# MAIN.net
KiCad netlist of a schematic drawn in Altium Designer
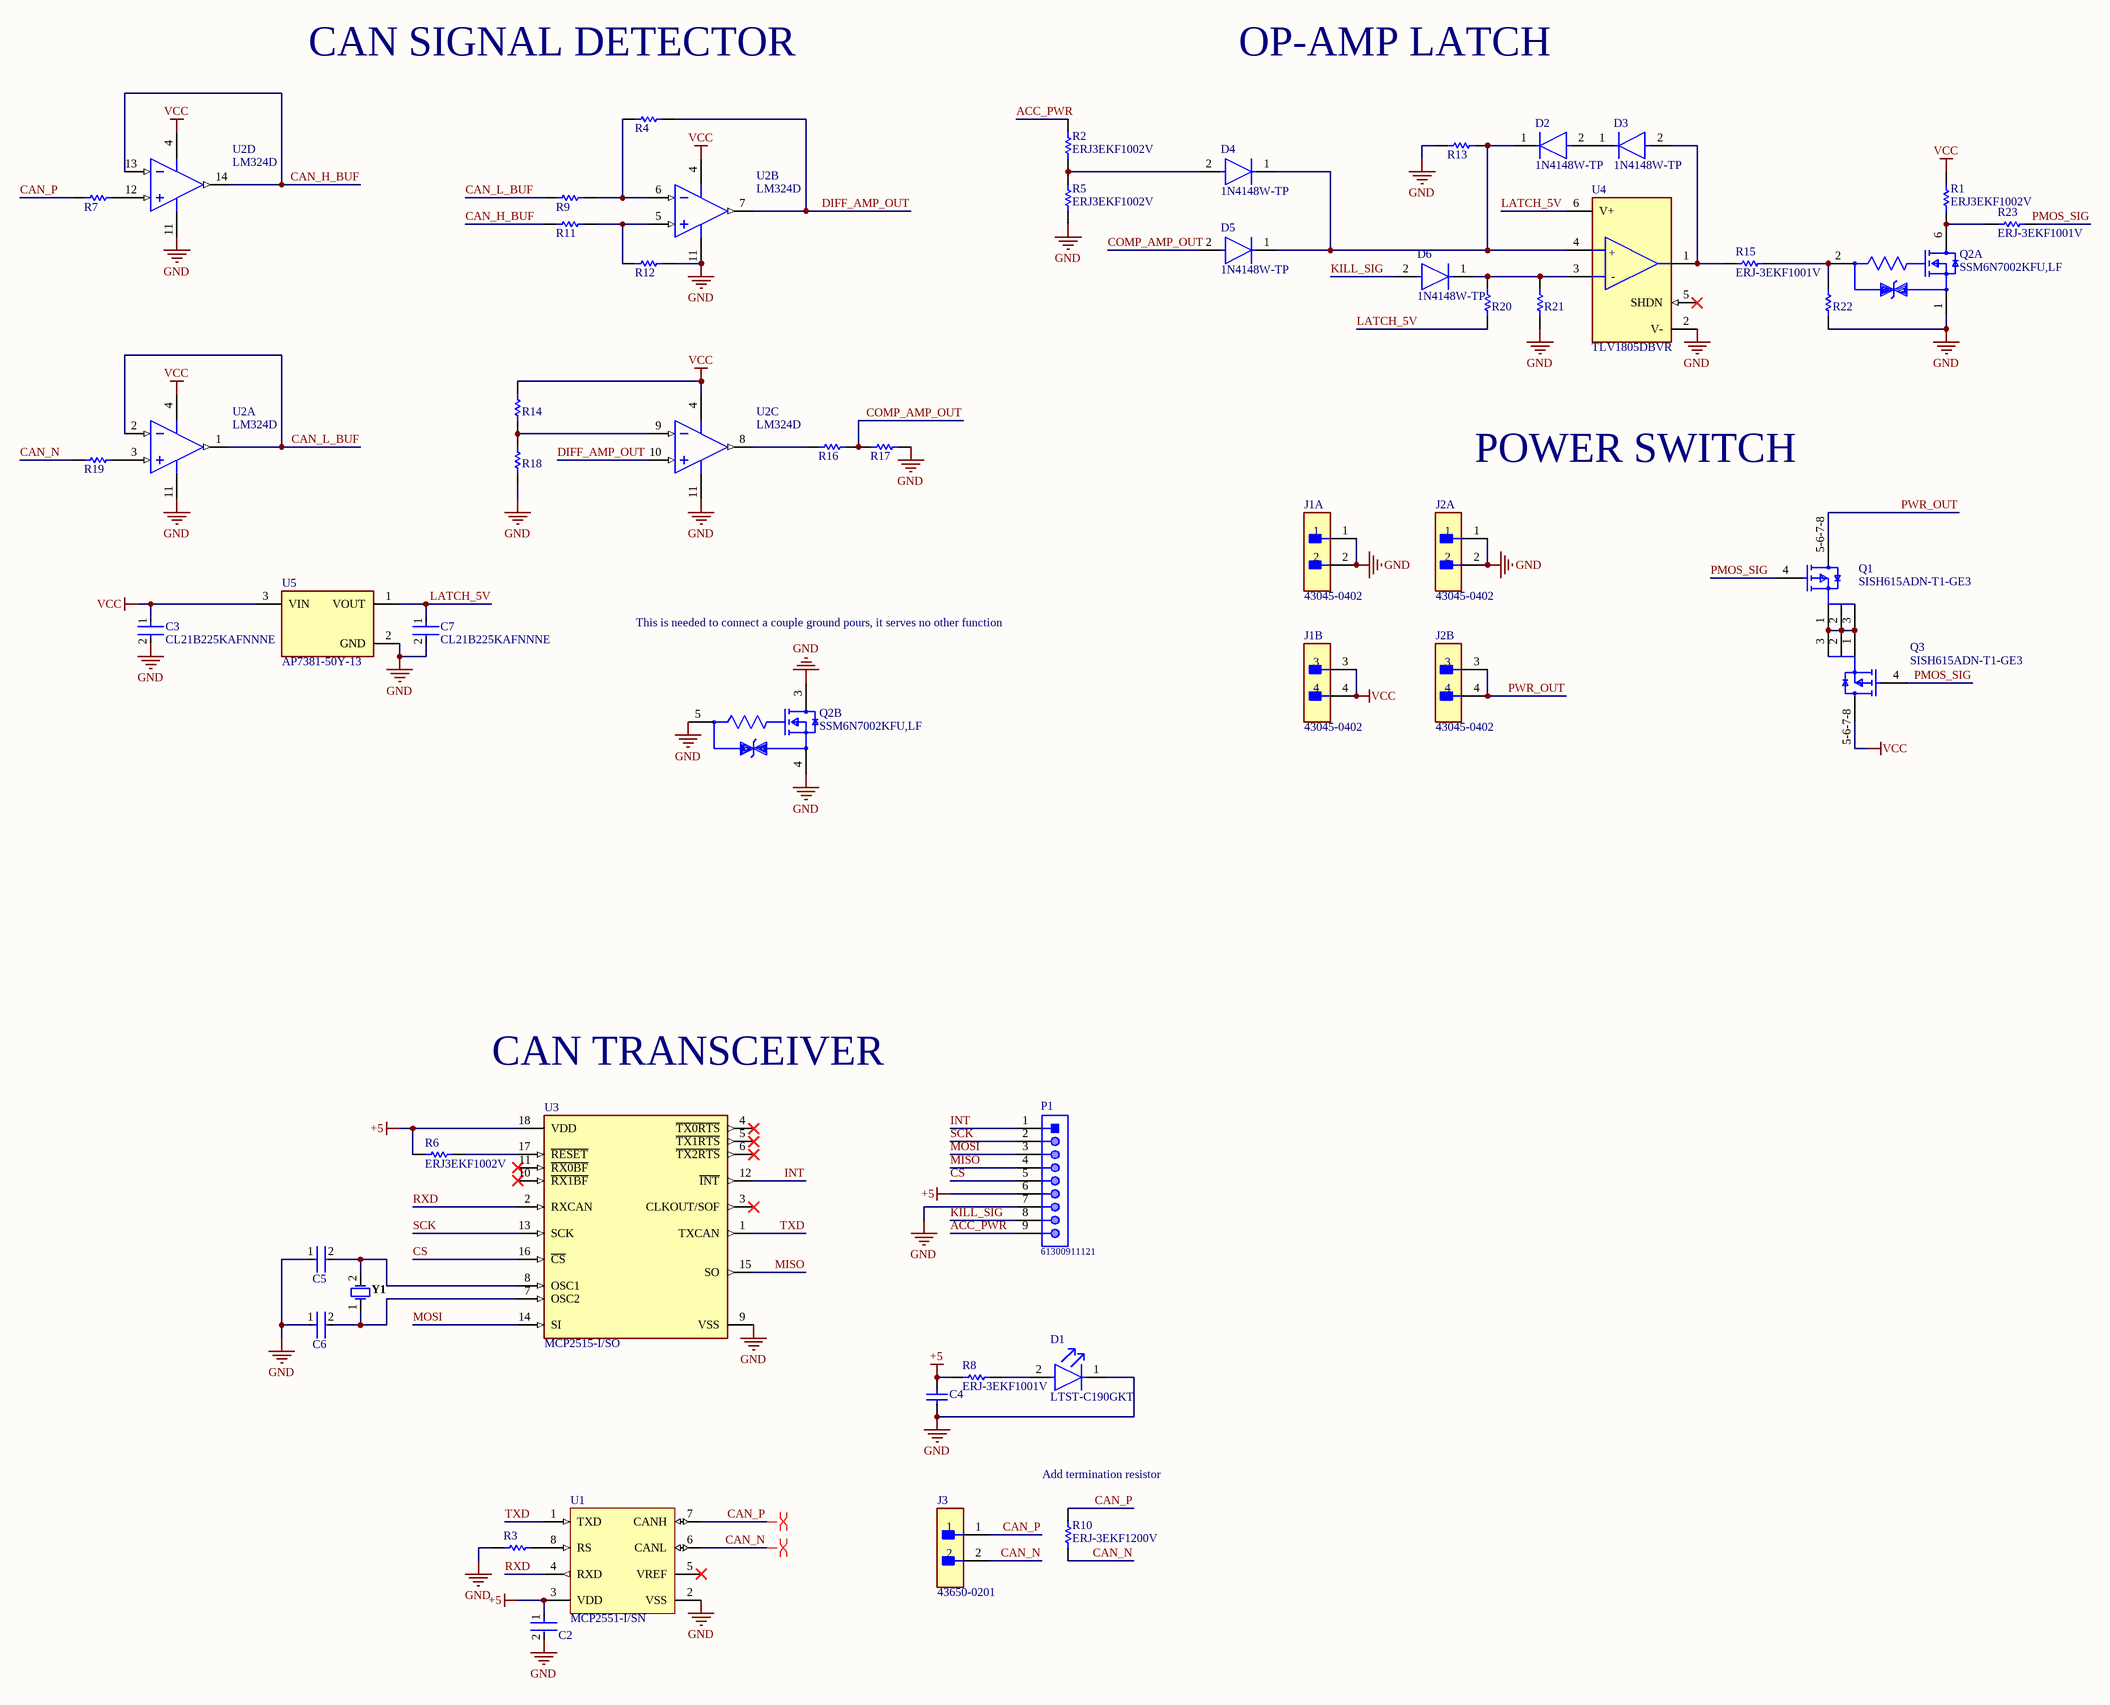
[diagram p0: MAIN.SchDoc]

(export (version "E")
  (design (tool "Eeschema 10.0.6"))
  (components
    (comp (ref "C2")
      (value "C0402C104K8PACTU")
      (footprint "FP-C0402-BB-MFG")
      (description "CAP CER 0.1UF 10V X5R 0402")
      (fields (field (name "MANUFACTURER") "Kemet") (field (name "TOLERANCE") "0.1"))
      (libsource (lib "Altium Content Vault") (part "b4654b650e69147ec39a6b967a45e02"))
    )
    (comp (ref "C3")
      (value "CL21B225KAFNNNE")
      (footprint "FP-0805-L_2_01_0_2-W_1_25-IPC_B")
      (fields (field (name "TOLERANCE") "10%") (field (name "VOLTAGE") "25V"))
      (libsource (lib "Altium Content Vault") (part "02cd4be3c70576c341d710602a673aa"))
    )
    (comp (ref "C4")
      (value "1206GC102KAT1A")
      (footprint "AVX-1206-2_L")
      (description "Chip Capacitor, 1 nF, +/- 10%, -55 to 125 degC, 1206 (3216 Metric), RoHS, Tape and Reel")
      (fields (field (name "TOLERANCE") "10%") (field (name "MANUFACTURER") "AVX"))
      (libsource (lib "Altium Content Vault") (part "CAP-NP-2"))
    )
    (comp (ref "C5")
      (value "GRM188R60J106ME47D")
      (footprint "FP-GRM188-0_1-e0_2_0_55-IPC_A")
      (description "Chip Multilayer Ceramic Capacitors for General Purpose, 0603, 10uF, X5R, 15%, 20%, 6.3V")
      (fields (field (name "VOLTAGE") "6.3V") (field (name "TOLERANCE") "20%"))
      (libsource (lib "Altium Content Vault") (part "02cd4be3c70576c341d710602a673aa"))
    )
    (comp (ref "C6")
      (value "GRM188R60J106ME47D")
      (footprint "FP-GRM188-0_1-e0_2_0_55-IPC_A")
      (description "Chip Multilayer Ceramic Capacitors for General Purpose, 0603, 10uF, X5R, 15%, 20%, 6.3V")
      (fields (field (name "VOLTAGE") "6.3V") (field (name "TOLERANCE") "20%"))
      (libsource (lib "Altium Content Vault") (part "02cd4be3c70576c341d710602a673aa"))
    )
    (comp (ref "C7")
      (value "CL21B225KAFNNNE")
      (footprint "FP-0805-L_2_01_0_2-W_1_25-IPC_B")
      (fields (field (name "TOLERANCE") "10%") (field (name "VOLTAGE") "25V"))
      (libsource (lib "Altium Content Vault") (part "02cd4be3c70576c341d710602a673aa"))
    )
    (comp (ref "D1")
      (value "LTST-C190GKT")
      (footprint "FP-LTST-C190GKT-MFG")
      (description "LED GREEN CLEAR CHIP SMD")
      (fields (field (name "VOLTAGE") "2V"))
      (libsource (lib "Altium Content Vault") (part "8706943c75ba83719d021d2fdc84c58"))
    )
    (comp (ref "D2")
      (value "1N4148W-TP")
      (footprint "FP-SOD-123-IPC_A")
      (description "DIODE GEN PURP 100V 150MA SOD123")
      (libsource (lib "Altium Content Vault") (part "d7152d700b627762746794eb795d46e"))
    )
    (comp (ref "D3")
      (value "1N4148W-TP")
      (footprint "FP-SOD-123-IPC_A")
      (description "DIODE GEN PURP 100V 150MA SOD123")
      (libsource (lib "Altium Content Vault") (part "d7152d700b627762746794eb795d46e"))
    )
    (comp (ref "D4")
      (value "1N4148W-TP")
      (footprint "FP-SOD-123-IPC_A")
      (description "DIODE GEN PURP 100V 150MA SOD123")
      (libsource (lib "Altium Content Vault") (part "d7152d700b627762746794eb795d46e"))
    )
    (comp (ref "D5")
      (value "1N4148W-TP")
      (footprint "FP-SOD-123-IPC_A")
      (description "DIODE GEN PURP 100V 150MA SOD123")
      (libsource (lib "Altium Content Vault") (part "d7152d700b627762746794eb795d46e"))
    )
    (comp (ref "D6")
      (value "1N4148W-TP")
      (footprint "FP-SOD-123-IPC_A")
      (description "DIODE GEN PURP 100V 150MA SOD123")
      (libsource (lib "Altium Content Vault") (part "d7152d700b627762746794eb795d46e"))
    )
    (comp (ref "J1")
      (value "43045-0402")
      (footprint "FP-43045-0402-MFG")
      (description "CONN HEADER R/A 4POS 3MM")
      (libsource (lib "Altium Content Vault") (part "ac72c5313ea981db199dbd0e8237b04"))
    )
    (comp (ref "J2")
      (value "43045-0402")
      (footprint "FP-43045-0402-MFG")
      (description "CONN HEADER R/A 4POS 3MM")
      (libsource (lib "Altium Content Vault") (part "ac72c5313ea981db199dbd0e8237b04"))
    )
    (comp (ref "J3")
      (value "43650-0201")
      (footprint "FP-43650-0201-MFG")
      (description "CONN HEADER R/A 2POS 3MM")
      (libsource (lib "Altium Content Vault") (part "3bc925449376181038e59eaffc5286c"))
    )
    (comp (ref "P1")
      (value "61300911121")
      (footprint "61300911121")
      (description "THT Vertical Pin Header WR-PHD, Pitch 2.54 mm, Single Row, 9 pins")
      (fields (field (name "MANUFACTURER") "Wurth Elektronik") (field (name "PUBLISHER") "WurthElektronik"))
      (libsource (lib "Altium Content Vault") (part "WE-CN-1P-M-R9"))
    )
    (comp (ref "Q1")
      (value "SISH615ADN-T1-GE3")
      (footprint "SISH615ADN-T1-GE3-Footprint-1")
      (description "Trans MOSFET P-CH 20V 22.1A 8-Pin PowerPAK 1212 EP T/R")
      (libsource (lib "uORocketry Hardware") (part "SISH615ADN-T1-GE3-Symbol-1"))
    )
    (comp (ref "Q2")
      (value "SSM6N7002KFU,LF")
      (footprint "FP-SSOP6-P-0_65A-MFG")
      (description "MOSFET 2N-CH 60V 0.3A")
      (libsource (lib "Altium Content Vault") (part "088aa6ac103fdeebe0d1c52ece6b7b9"))
    )
    (comp (ref "Q3")
      (value "SISH615ADN-T1-GE3")
      (footprint "SISH615ADN-T1-GE3-Footprint-1")
      (description "Trans MOSFET P-CH 20V 22.1A 8-Pin PowerPAK 1212 EP T/R")
      (libsource (lib "uORocketry Hardware") (part "SISH615ADN-T1-GE3-Symbol-1"))
    )
    (comp (ref "R1")
      (value "ERJ3EKF1002V")
      (footprint "RESC1609X55X30LL15T15")
      (description "Chip Resistor, 10 KOhm, +/- 1%, 0.1 W, -55 to 155 degC, 0603 (1608 Metric), RoHS, Tape and Reel")
      (fields (field (name "TOLERANCE") "1%") (field (name "MANUFACTURER") "Panasonic"))
      (libsource (lib "Altium Content Vault") (part "RES-2"))
    )
    (comp (ref "R2")
      (value "ERJ3EKF1002V")
      (footprint "RESC1609X55X30LL15T15")
      (description "Chip Resistor, 10 KOhm, +/- 1%, 0.1 W, -55 to 155 degC, 0603 (1608 Metric), RoHS, Tape and Reel")
      (fields (field (name "TOLERANCE") "1%") (field (name "MANUFACTURER") "Panasonic"))
      (libsource (lib "Altium Content Vault") (part "RES-2"))
    )
    (comp (ref "R3")
      (value "ERJ3EKF1002V")
      (footprint "RESC1609X55X30LL15T15")
      (description "Chip Resistor, 10 KOhm, +/- 1%, 0.1 W, -55 to 155 degC, 0603 (1608 Metric), RoHS, Tape and Reel")
      (fields (field (name "TOLERANCE") "1%") (field (name "MANUFACTURER") "Panasonic"))
      (libsource (lib "Altium Content Vault") (part "RES-2"))
    )
    (comp (ref "R4")
      (value "ERJ3EKF1002V")
      (footprint "RESC1609X55X30LL15T15")
      (description "Chip Resistor, 10 KOhm, +/- 1%, 0.1 W, -55 to 155 degC, 0603 (1608 Metric), RoHS, Tape and Reel")
      (fields (field (name "TOLERANCE") "1%") (field (name "MANUFACTURER") "Panasonic"))
      (libsource (lib "Altium Content Vault") (part "RES-2"))
    )
    (comp (ref "R5")
      (value "ERJ3EKF1002V")
      (footprint "RESC1609X55X30LL15T15")
      (description "Chip Resistor, 10 KOhm, +/- 1%, 0.1 W, -55 to 155 degC, 0603 (1608 Metric), RoHS, Tape and Reel")
      (fields (field (name "TOLERANCE") "1%") (field (name "MANUFACTURER") "Panasonic"))
      (libsource (lib "Altium Content Vault") (part "RES-2"))
    )
    (comp (ref "R6")
      (value "ERJ3EKF1002V")
      (footprint "RESC1609X55X30LL15T15")
      (description "Chip Resistor, 10 KOhm, +/- 1%, 0.1 W, -55 to 155 degC, 0603 (1608 Metric), RoHS, Tape and Reel")
      (fields (field (name "TOLERANCE") "1%") (field (name "MANUFACTURER") "Panasonic"))
      (libsource (lib "Altium Content Vault") (part "RES-2"))
    )
    (comp (ref "R7")
      (value "ERJ3EKF1002V")
      (footprint "RESC1609X55X30LL15T15")
      (description "Chip Resistor, 10 KOhm, +/- 1%, 0.1 W, -55 to 155 degC, 0603 (1608 Metric), RoHS, Tape and Reel")
      (fields (field (name "TOLERANCE") "1%") (field (name "MANUFACTURER") "Panasonic"))
      (libsource (lib "Altium Content Vault") (part "RES-2"))
    )
    (comp (ref "R8")
      (value "ERJ-3EKF1001V")
      (footprint "RESC1608X55X30LL15T15")
      (fields (field (name "MANUFACTURER") "Panasonic"))
      (libsource (lib "Altium Content Vault") (part "RES"))
    )
    (comp (ref "R9")
      (value "ERJ3EKF1002V")
      (footprint "RESC1609X55X30LL15T15")
      (description "Chip Resistor, 10 KOhm, +/- 1%, 0.1 W, -55 to 155 degC, 0603 (1608 Metric), RoHS, Tape and Reel")
      (fields (field (name "TOLERANCE") "1%") (field (name "MANUFACTURER") "Panasonic"))
      (libsource (lib "Altium Content Vault") (part "RES-2"))
    )
    (comp (ref "R10")
      (value "ERJ-3EKF1200V")
      (footprint "RESC1609X55X30ML15T15")
      (description "Chip Resistor, 120 Ohm, +/- 1%, 0.1 W, -55 to 155 degC, 0603 (1608 Metric), RoHS, Tape and Reel")
      (fields (field (name "TOLERANCE") "1%") (field (name "MANUFACTURER") "Panasonic"))
      (libsource (lib "Altium Content Vault") (part "RES-2"))
    )
    (comp (ref "R11")
      (value "ERJ3EKF1002V")
      (footprint "RESC1609X55X30LL15T15")
      (description "Chip Resistor, 10 KOhm, +/- 1%, 0.1 W, -55 to 155 degC, 0603 (1608 Metric), RoHS, Tape and Reel")
      (fields (field (name "TOLERANCE") "1%") (field (name "MANUFACTURER") "Panasonic"))
      (libsource (lib "Altium Content Vault") (part "RES-2"))
    )
    (comp (ref "R12")
      (value "ERJ3EKF1002V")
      (footprint "RESC1609X55X30LL15T15")
      (description "Chip Resistor, 10 KOhm, +/- 1%, 0.1 W, -55 to 155 degC, 0603 (1608 Metric), RoHS, Tape and Reel")
      (fields (field (name "TOLERANCE") "1%") (field (name "MANUFACTURER") "Panasonic"))
      (libsource (lib "Altium Content Vault") (part "RES-2"))
    )
    (comp (ref "R13")
      (value "ERJ3EKF1002V")
      (footprint "RESC1609X55X30LL15T15")
      (description "Chip Resistor, 10 KOhm, +/- 1%, 0.1 W, -55 to 155 degC, 0603 (1608 Metric), RoHS, Tape and Reel")
      (fields (field (name "TOLERANCE") "1%") (field (name "MANUFACTURER") "Panasonic"))
      (libsource (lib "Altium Content Vault") (part "RES-2"))
    )
    (comp (ref "R14")
      (value "ERJ3EKF1002V")
      (footprint "RESC1609X55X30LL15T15")
      (description "Chip Resistor, 10 KOhm, +/- 1%, 0.1 W, -55 to 155 degC, 0603 (1608 Metric), RoHS, Tape and Reel")
      (fields (field (name "TOLERANCE") "1%") (field (name "MANUFACTURER") "Panasonic"))
      (libsource (lib "Altium Content Vault") (part "RES-2"))
    )
    (comp (ref "R15")
      (value "ERJ-3EKF1001V")
      (footprint "RESC1608X55X30LL15T15")
      (fields (field (name "MANUFACTURER") "Panasonic"))
      (libsource (lib "Altium Content Vault") (part "RES"))
    )
    (comp (ref "R16")
      (value "ERJ3EKF1002V")
      (footprint "RESC1609X55X30LL15T15")
      (description "Chip Resistor, 10 KOhm, +/- 1%, 0.1 W, -55 to 155 degC, 0603 (1608 Metric), RoHS, Tape and Reel")
      (fields (field (name "TOLERANCE") "1%") (field (name "MANUFACTURER") "Panasonic"))
      (libsource (lib "Altium Content Vault") (part "RES-2"))
    )
    (comp (ref "R17")
      (value "ERJ3EKF1002V")
      (footprint "RESC1609X55X30LL15T15")
      (description "Chip Resistor, 10 KOhm, +/- 1%, 0.1 W, -55 to 155 degC, 0603 (1608 Metric), RoHS, Tape and Reel")
      (fields (field (name "TOLERANCE") "1%") (field (name "MANUFACTURER") "Panasonic"))
      (libsource (lib "Altium Content Vault") (part "RES-2"))
    )
    (comp (ref "R18")
      (value "ERJ-3EKF1001V")
      (footprint "RESC1608X55X30LL15T15")
      (fields (field (name "MANUFACTURER") "Panasonic"))
      (libsource (lib "Altium Content Vault") (part "RES"))
    )
    (comp (ref "R19")
      (value "ERJ3EKF1002V")
      (footprint "RESC1609X55X30LL15T15")
      (description "Chip Resistor, 10 KOhm, +/- 1%, 0.1 W, -55 to 155 degC, 0603 (1608 Metric), RoHS, Tape and Reel")
      (fields (field (name "TOLERANCE") "1%") (field (name "MANUFACTURER") "Panasonic"))
      (libsource (lib "Altium Content Vault") (part "RES-2"))
    )
    (comp (ref "R20")
      (value "ERJ3EKF1002V")
      (footprint "RESC1609X55X30LL15T15")
      (description "Chip Resistor, 10 KOhm, +/- 1%, 0.1 W, -55 to 155 degC, 0603 (1608 Metric), RoHS, Tape and Reel")
      (fields (field (name "TOLERANCE") "1%") (field (name "MANUFACTURER") "Panasonic"))
      (libsource (lib "Altium Content Vault") (part "RES-2"))
    )
    (comp (ref "R21")
      (value "ERJ3EKF1002V")
      (footprint "RESC1609X55X30LL15T15")
      (description "Chip Resistor, 10 KOhm, +/- 1%, 0.1 W, -55 to 155 degC, 0603 (1608 Metric), RoHS, Tape and Reel")
      (fields (field (name "TOLERANCE") "1%") (field (name "MANUFACTURER") "Panasonic"))
      (libsource (lib "Altium Content Vault") (part "RES-2"))
    )
    (comp (ref "R22")
      (value "ERJ3EKF1002V")
      (footprint "RESC1609X55X30LL15T15")
      (description "Chip Resistor, 10 KOhm, +/- 1%, 0.1 W, -55 to 155 degC, 0603 (1608 Metric), RoHS, Tape and Reel")
      (fields (field (name "TOLERANCE") "1%") (field (name "MANUFACTURER") "Panasonic"))
      (libsource (lib "Altium Content Vault") (part "RES-2"))
    )
    (comp (ref "R23")
      (value "ERJ-3EKF1001V")
      (footprint "RESC1608X55X30LL15T15")
      (fields (field (name "MANUFACTURER") "Panasonic"))
      (libsource (lib "Altium Content Vault") (part "RES"))
    )
    (comp (ref "U1")
      (value "MCP2551-I/SN")
      (footprint "MCHP-SN8_V")
      (fields (field (name "MANUFACTURER") "Microchip"))
      (libsource (lib "Altium Content Vault") (part "MCHP-MCP2551-SN8"))
    )
    (comp (ref "U2")
      (value "LM324D")
      (footprint "D0014A_L")
      (fields (field (name "MANUFACTURER") "Texas Instruments"))
      (libsource (lib "Altium Content Vault") (part "TI-LMX24_2902X-X14"))
    )
    (comp (ref "U3")
      (value "MCP2515-I/SO")
      (footprint "FP-C04-051-MFG")
      (description "IC CAN CONTROLLER W/SPI 18SOIC")
      (fields
        (field (name "MANUFACTURER") "Microchip")
        (field (name "OCTOPART") "https://octopart.com/mcp2515-i%2Fso-microchip-430187")
      )
      (libsource (lib "Altium Content Vault") (part "1c78ea6ff576bac94664e2637e1b479"))
    )
    (comp (ref "U4")
      (value "TLV1805DBVR")
      (footprint "FP-DBV0006A-IPC_C")
      (description "40V, RAIL-TO-RAIL INPUT, PUSH-PU")
      (libsource (lib "Altium Content Vault") (part "c7aa3bc3dbf0dc8b0b0354779bd1228"))
    )
    (comp (ref "U5")
      (value "AP7381-50Y-13")
      (footprint "FP-SOT89-MFG")
      (description "IC REG LINEAR 5V 150MA SOT89")
      (fields
        (field (name "MANUFACTURER") "Diodes Inc.")
        (field (name "OCTOPART") "https://octopart.com/ap7381-50y-13-diodes+inc.-87775116")
      )
      (libsource (lib "Altium Content Vault") (part "4c3da590f2d7b1882ad42f13e6d336b"))
    )
    (comp (ref "Y1")
      (value "FOXSLF/160-20")
      (footprint "FOX-FOXSLF160-20")
      (description "Resistance Weld Thru-Hole Crystal, 16 MHz, -20 to 70 degC, 2-Pin THD, RoHS, Bulk")
      (fields (field (name "TOLERANCE") "1%"))
      (libsource (lib "Altium Content Vault") (part "XTAL-1-2-2"))
    )
  )
  (nets
    (net (code "1") (name "+5") (class "Default")
      (node (ref "C2") (pin "1") (pinfunction "1_1") (pintype "passive"))
      (node (ref "C4") (pin "2") (pinfunction "2_2") (pintype "passive"))
      (node (ref "P1") (pin "6") (pinfunction "6_6") (pintype "passive"))
      (node (ref "R6") (pin "1") (pinfunction "1_1") (pintype "passive"))
      (node (ref "R8") (pin "2") (pinfunction "2_2") (pintype "passive"))
      (node (ref "U1") (pin "3") (pinfunction "VDD_3") (pintype "power_in"))
      (node (ref "U3") (pin "18") (pinfunction "VDD_18") (pintype "power_in"))
    )
    (net (code "2") (name "/ACC_PWR") (class "Default")
      (node (ref "P1") (pin "9") (pinfunction "9_9") (pintype "passive"))
      (node (ref "R2") (pin "2") (pinfunction "2_2") (pintype "passive"))
    )
    (net (code "3") (name "/CAN_H_BUF") (class "Default")
      (node (ref "R11") (pin "1") (pinfunction "1_1") (pintype "passive"))
      (node (ref "U2") (pin "13") (pinfunction "4IN-_13") (pintype "input"))
      (node (ref "U2") (pin "14") (pinfunction "4OUT_14") (pintype "output"))
    )
    (net (code "4") (name "/CAN_L_BUF") (class "Default")
      (node (ref "R9") (pin "1") (pinfunction "1_1") (pintype "passive"))
      (node (ref "U2") (pin "1") (pinfunction "1OUT_1") (pintype "output"))
      (node (ref "U2") (pin "2") (pinfunction "1IN-_2") (pintype "input"))
    )
    (net (code "5") (name "/CAN_N") (class "Default")
      (node (ref "J3") (pin "2") (pinfunction "2_2") (pintype "passive"))
      (node (ref "R10") (pin "1") (pinfunction "1_1") (pintype "passive"))
      (node (ref "R19") (pin "1") (pinfunction "1_1") (pintype "passive"))
      (node (ref "U1") (pin "6") (pinfunction "CANL_6") (pintype "bidirectional"))
    )
    (net (code "6") (name "/CAN_P") (class "Default")
      (node (ref "J3") (pin "1") (pinfunction "1_1") (pintype "passive"))
      (node (ref "R10") (pin "2") (pinfunction "2_2") (pintype "passive"))
      (node (ref "R7") (pin "1") (pinfunction "1_1") (pintype "passive"))
      (node (ref "U1") (pin "7") (pinfunction "CANH_7") (pintype "bidirectional"))
    )
    (net (code "7") (name "/COMP_AMP_OUT") (class "Default")
      (node (ref "D5") (pin "2") (pinfunction "A_2") (pintype "passive"))
      (node (ref "R16") (pin "1") (pinfunction "1_1") (pintype "passive"))
      (node (ref "R17") (pin "2") (pinfunction "2_2") (pintype "passive"))
    )
    (net (code "8") (name "/CS") (class "Default")
      (node (ref "P1") (pin "5") (pinfunction "5_5") (pintype "passive"))
      (node (ref "U3") (pin "16") (pinfunction "~{CS}_16") (pintype "input"))
    )
    (net (code "9") (name "/DIFF_AMP_OUT") (class "Default")
      (node (ref "R4") (pin "2") (pinfunction "2_2") (pintype "passive"))
      (node (ref "U2") (pin "10") (pinfunction "3IN+_10") (pintype "input"))
      (node (ref "U2") (pin "7") (pinfunction "2OUT_7") (pintype "output"))
    )
    (net (code "10") (name "/INT") (class "Default")
      (node (ref "P1") (pin "1") (pinfunction "1_1") (pintype "passive"))
      (node (ref "U3") (pin "12") (pinfunction "~{INT}_12") (pintype "output"))
    )
    (net (code "11") (name "/KILL_SIG") (class "Default")
      (node (ref "D6") (pin "2") (pinfunction "A_2") (pintype "passive"))
      (node (ref "P1") (pin "8") (pinfunction "8_8") (pintype "passive"))
    )
    (net (code "12") (name "/LATCH_5V") (class "Default")
      (node (ref "C7") (pin "1") (pinfunction "1_1") (pintype "passive"))
      (node (ref "R20") (pin "1") (pinfunction "1_1") (pintype "passive"))
      (node (ref "U4") (pin "6") (pinfunction "V+_6") (pintype "power_in"))
      (node (ref "U5") (pin "1") (pinfunction "VOUT_1") (pintype "power_in"))
    )
    (net (code "13") (name "/MISO") (class "Default")
      (node (ref "P1") (pin "4") (pinfunction "4_4") (pintype "passive"))
      (node (ref "U3") (pin "15") (pinfunction "SO_15") (pintype "output"))
    )
    (net (code "14") (name "/MOSI") (class "Default")
      (node (ref "P1") (pin "3") (pinfunction "3_3") (pintype "passive"))
      (node (ref "U3") (pin "14") (pinfunction "SI_14") (pintype "input"))
    )
    (net (code "15") (name "/PMOS_SIG") (class "Default")
      (node (ref "Q1") (pin "4") (pinfunction "G_4") (pintype "passive"))
      (node (ref "Q3") (pin "4") (pinfunction "G_4") (pintype "passive"))
      (node (ref "R23") (pin "1") (pinfunction "1_1") (pintype "passive"))
    )
    (net (code "16") (name "/PWR_OUT") (class "Default")
      (node (ref "J2") (pin "3") (pinfunction "3_3") (pintype "passive"))
      (node (ref "J2") (pin "4") (pinfunction "4_4") (pintype "passive"))
      (node (ref "Q1") (pin "5-6-7-8") (pinfunction "D_5-6-7-8") (pintype "passive"))
    )
    (net (code "17") (name "/RXD") (class "Default")
      (node (ref "U1") (pin "4") (pinfunction "RXD_4") (pintype "output"))
      (node (ref "U3") (pin "2") (pinfunction "RXCAN_2") (pintype "input"))
    )
    (net (code "18") (name "/SCK") (class "Default")
      (node (ref "P1") (pin "2") (pinfunction "2_2") (pintype "passive"))
      (node (ref "U3") (pin "13") (pinfunction "SCK_13") (pintype "input"))
    )
    (net (code "19") (name "/TXD") (class "Default")
      (node (ref "U1") (pin "1") (pinfunction "TXD_1") (pintype "input"))
      (node (ref "U3") (pin "1") (pinfunction "TXCAN_1") (pintype "output"))
    )
    (net (code "20") (name "GND") (class "Default")
      (node (ref "C2") (pin "2") (pinfunction "2_2") (pintype "passive"))
      (node (ref "C3") (pin "2") (pinfunction "2_2") (pintype "passive"))
      (node (ref "C4") (pin "1") (pinfunction "1_1") (pintype "passive"))
      (node (ref "C5") (pin "1") (pinfunction "1_1") (pintype "passive"))
      (node (ref "C6") (pin "1") (pinfunction "1_1") (pintype "passive"))
      (node (ref "C7") (pin "2") (pinfunction "2_2") (pintype "passive"))
      (node (ref "D1") (pin "1") (pinfunction "C_1") (pintype "passive"))
      (node (ref "J1") (pin "1") (pinfunction "1_1") (pintype "passive"))
      (node (ref "J1") (pin "2") (pinfunction "2_2") (pintype "passive"))
      (node (ref "J2") (pin "1") (pinfunction "1_1") (pintype "passive"))
      (node (ref "J2") (pin "2") (pinfunction "2_2") (pintype "passive"))
      (node (ref "P1") (pin "7") (pinfunction "7_7") (pintype "passive"))
      (node (ref "Q2") (pin "1") (pinfunction "Source1_1") (pintype "passive"))
      (node (ref "Q2") (pin "3") (pinfunction "Drain2_3") (pintype "passive"))
      (node (ref "Q2") (pin "4") (pinfunction "Source2_4") (pintype "passive"))
      (node (ref "Q2") (pin "5") (pinfunction "Gate2_5") (pintype "passive"))
      (node (ref "R12") (pin "2") (pinfunction "2_2") (pintype "passive"))
      (node (ref "R13") (pin "2") (pinfunction "2_2") (pintype "passive"))
      (node (ref "R17") (pin "1") (pinfunction "1_1") (pintype "passive"))
      (node (ref "R18") (pin "1") (pinfunction "1_1") (pintype "passive"))
      (node (ref "R21") (pin "1") (pinfunction "1_1") (pintype "passive"))
      (node (ref "R22") (pin "2") (pinfunction "2_2") (pintype "passive"))
      (node (ref "R3") (pin "1") (pinfunction "1_1") (pintype "passive"))
      (node (ref "R5") (pin "1") (pinfunction "1_1") (pintype "passive"))
      (node (ref "U1") (pin "2") (pinfunction "VSS_2") (pintype "power_in"))
      (node (ref "U2") (pin "11") (pinfunction "GND_11") (pintype "power_in"))
      (node (ref "U3") (pin "9") (pinfunction "VSS_9") (pintype "power_in"))
      (node (ref "U4") (pin "2") (pinfunction "V-_2") (pintype "power_in"))
      (node (ref "U5") (pin "2") (pinfunction "GND_2") (pintype "power_in"))
    )
    (net (code "21") (name "Net-(D1-A)") (class "Default")
      (node (ref "D1") (pin "2") (pinfunction "A_2") (pintype "passive"))
      (node (ref "R8") (pin "1") (pinfunction "1_1") (pintype "passive"))
    )
    (net (code "22") (name "Net-(D2-A)") (class "Default")
      (node (ref "D2") (pin "2") (pinfunction "A_2") (pintype "passive"))
      (node (ref "D3") (pin "1") (pinfunction "C_1") (pintype "passive"))
    )
    (net (code "23") (name "Net-(D2-C)") (class "Default")
      (node (ref "D2") (pin "1") (pinfunction "C_1") (pintype "passive"))
      (node (ref "D4") (pin "1") (pinfunction "C_1") (pintype "passive"))
      (node (ref "D5") (pin "1") (pinfunction "C_1") (pintype "passive"))
      (node (ref "R13") (pin "1") (pinfunction "1_1") (pintype "passive"))
      (node (ref "U4") (pin "4") (pinfunction "+IN_4") (pintype "tri_state"))
    )
    (net (code "24") (name "Net-(D3-A)") (class "Default")
      (node (ref "D3") (pin "2") (pinfunction "A_2") (pintype "passive"))
      (node (ref "R15") (pin "2") (pinfunction "2_2") (pintype "passive"))
      (node (ref "U4") (pin "1") (pinfunction "OUT_1") (pintype "passive"))
    )
    (net (code "25") (name "Net-(D4-A)") (class "Default")
      (node (ref "D4") (pin "2") (pinfunction "A_2") (pintype "passive"))
      (node (ref "R2") (pin "1") (pinfunction "1_1") (pintype "passive"))
      (node (ref "R5") (pin "2") (pinfunction "2_2") (pintype "passive"))
    )
    (net (code "26") (name "Net-(D6-C)") (class "Default")
      (node (ref "D6") (pin "1") (pinfunction "C_1") (pintype "passive"))
      (node (ref "R20") (pin "2") (pinfunction "2_2") (pintype "passive"))
      (node (ref "R21") (pin "2") (pinfunction "2_2") (pintype "passive"))
      (node (ref "U4") (pin "3") (pinfunction "-IN_3") (pintype "tri_state"))
    )
    (net (code "27") (name "Net-(Q1-S-Pad1)") (class "Default")
      (node (ref "Q1") (pin "1") (pinfunction "S_1") (pintype "passive"))
      (node (ref "Q1") (pin "2") (pinfunction "S_2") (pintype "passive"))
      (node (ref "Q1") (pin "3") (pinfunction "S_3") (pintype "passive"))
      (node (ref "Q3") (pin "1") (pinfunction "S_1") (pintype "passive"))
      (node (ref "Q3") (pin "2") (pinfunction "S_2") (pintype "passive"))
      (node (ref "Q3") (pin "3") (pinfunction "S_3") (pintype "passive"))
    )
    (net (code "28") (name "Net-(Q2A-Drain1)") (class "Default")
      (node (ref "Q2") (pin "6") (pinfunction "Drain1_6") (pintype "passive"))
      (node (ref "R1") (pin "1") (pinfunction "1_1") (pintype "passive"))
      (node (ref "R23") (pin "2") (pinfunction "2_2") (pintype "passive"))
    )
    (net (code "29") (name "Net-(Q2A-Gate1)") (class "Default")
      (node (ref "Q2") (pin "2") (pinfunction "Gate1_2") (pintype "passive"))
      (node (ref "R15") (pin "1") (pinfunction "1_1") (pintype "passive"))
      (node (ref "R22") (pin "1") (pinfunction "1_1") (pintype "passive"))
    )
    (net (code "30") (name "Net-(U1-RS)") (class "Default")
      (node (ref "R3") (pin "2") (pinfunction "2_2") (pintype "passive"))
      (node (ref "U1") (pin "8") (pinfunction "RS_8") (pintype "input"))
    )
    (net (code "31") (name "Net-(U2A-1IN+)") (class "Default")
      (node (ref "R19") (pin "2") (pinfunction "2_2") (pintype "passive"))
      (node (ref "U2") (pin "3") (pinfunction "1IN+_3") (pintype "input"))
    )
    (net (code "32") (name "Net-(U2B-2IN+)") (class "Default")
      (node (ref "R11") (pin "2") (pinfunction "2_2") (pintype "passive"))
      (node (ref "R12") (pin "1") (pinfunction "1_1") (pintype "passive"))
      (node (ref "U2") (pin "5") (pinfunction "2IN+_5") (pintype "input"))
    )
    (net (code "33") (name "Net-(U2B-2IN-)") (class "Default")
      (node (ref "R4") (pin "1") (pinfunction "1_1") (pintype "passive"))
      (node (ref "R9") (pin "2") (pinfunction "2_2") (pintype "passive"))
      (node (ref "U2") (pin "6") (pinfunction "2IN-_6") (pintype "input"))
    )
    (net (code "34") (name "Net-(U2C-3IN-)") (class "Default")
      (node (ref "R14") (pin "1") (pinfunction "1_1") (pintype "passive"))
      (node (ref "R18") (pin "2") (pinfunction "2_2") (pintype "passive"))
      (node (ref "U2") (pin "9") (pinfunction "3IN-_9") (pintype "input"))
    )
    (net (code "35") (name "Net-(U2C-3OUT)") (class "Default")
      (node (ref "R16") (pin "2") (pinfunction "2_2") (pintype "passive"))
      (node (ref "U2") (pin "8") (pinfunction "3OUT_8") (pintype "output"))
    )
    (net (code "36") (name "Net-(U2D-4IN+)") (class "Default")
      (node (ref "R7") (pin "2") (pinfunction "2_2") (pintype "passive"))
      (node (ref "U2") (pin "12") (pinfunction "4IN+_12") (pintype "input"))
    )
    (net (code "37") (name "Net-(U3-OSC1)") (class "Default")
      (node (ref "C5") (pin "2") (pinfunction "2_2") (pintype "passive"))
      (node (ref "U3") (pin "8") (pinfunction "OSC1_8") (pintype "input"))
      (node (ref "Y1") (pin "2") (pinfunction "2_2") (pintype "passive"))
    )
    (net (code "38") (name "Net-(U3-OSC2)") (class "Default")
      (node (ref "C6") (pin "2") (pinfunction "2_2") (pintype "passive"))
      (node (ref "U3") (pin "7") (pinfunction "OSC2_7") (pintype "input"))
      (node (ref "Y1") (pin "1") (pinfunction "1_1") (pintype "passive"))
    )
    (net (code "39") (name "Net-(U3-~{RESET})") (class "Default")
      (node (ref "R6") (pin "2") (pinfunction "2_2") (pintype "passive"))
      (node (ref "U3") (pin "17") (pinfunction "~{RESET}_17") (pintype "input"))
    )
    (net (code "40") (name "VCC") (class "Default")
      (node (ref "C3") (pin "1") (pinfunction "1_1") (pintype "passive"))
      (node (ref "J1") (pin "3") (pinfunction "3_3") (pintype "passive"))
      (node (ref "J1") (pin "4") (pinfunction "4_4") (pintype "passive"))
      (node (ref "Q3") (pin "5-6-7-8") (pinfunction "D_5-6-7-8") (pintype "passive"))
      (node (ref "R1") (pin "2") (pinfunction "2_2") (pintype "passive"))
      (node (ref "R14") (pin "2") (pinfunction "2_2") (pintype "passive"))
      (node (ref "U2") (pin "4") (pinfunction "VCC_4") (pintype "power_in"))
      (node (ref "U5") (pin "3") (pinfunction "VIN_3") (pintype "power_in"))
    )
    (net (code "41") (name "unconnected-(U1-VREF-Pad5)") (class "Default")
      (node (ref "U1") (pin "5") (pinfunction "VREF_5") (pintype "power_in+no_connect"))
    )
    (net (code "42") (name "unconnected-(U3-CLKOUT{slash}SOF-Pad3)") (class "Default")
      (node (ref "U3") (pin "3") (pinfunction "CLKOUT/SOF_3") (pintype "output+no_connect"))
    )
    (net (code "43") (name "unconnected-(U3-~{RX0BF}-Pad11)") (class "Default")
      (node (ref "U3") (pin "11") (pinfunction "~{RX0BF}_11") (pintype "input+no_connect"))
    )
    (net (code "44") (name "unconnected-(U3-~{RX1BF}-Pad10)") (class "Default")
      (node (ref "U3") (pin "10") (pinfunction "~{RX1BF}_10") (pintype "input+no_connect"))
    )
    (net (code "45") (name "unconnected-(U3-~{TX0RTS}-Pad4)") (class "Default")
      (node (ref "U3") (pin "4") (pinfunction "~{TX0RTS}_4") (pintype "output+no_connect"))
    )
    (net (code "46") (name "unconnected-(U3-~{TX1RTS}-Pad5)") (class "Default")
      (node (ref "U3") (pin "5") (pinfunction "~{TX1RTS}_5") (pintype "output+no_connect"))
    )
    (net (code "47") (name "unconnected-(U3-~{TX2RTS}-Pad6)") (class "Default")
      (node (ref "U3") (pin "6") (pinfunction "~{TX2RTS}_6") (pintype "output+no_connect"))
    )
    (net (code "48") (name "unconnected-(U4-SHDN-Pad5)") (class "Default")
      (node (ref "U4") (pin "5") (pinfunction "SHDN_5") (pintype "input+no_connect"))
    )
  )
)
